# SBH_MCU.net
KiCad netlist of a schematic drawn in Altium Designer
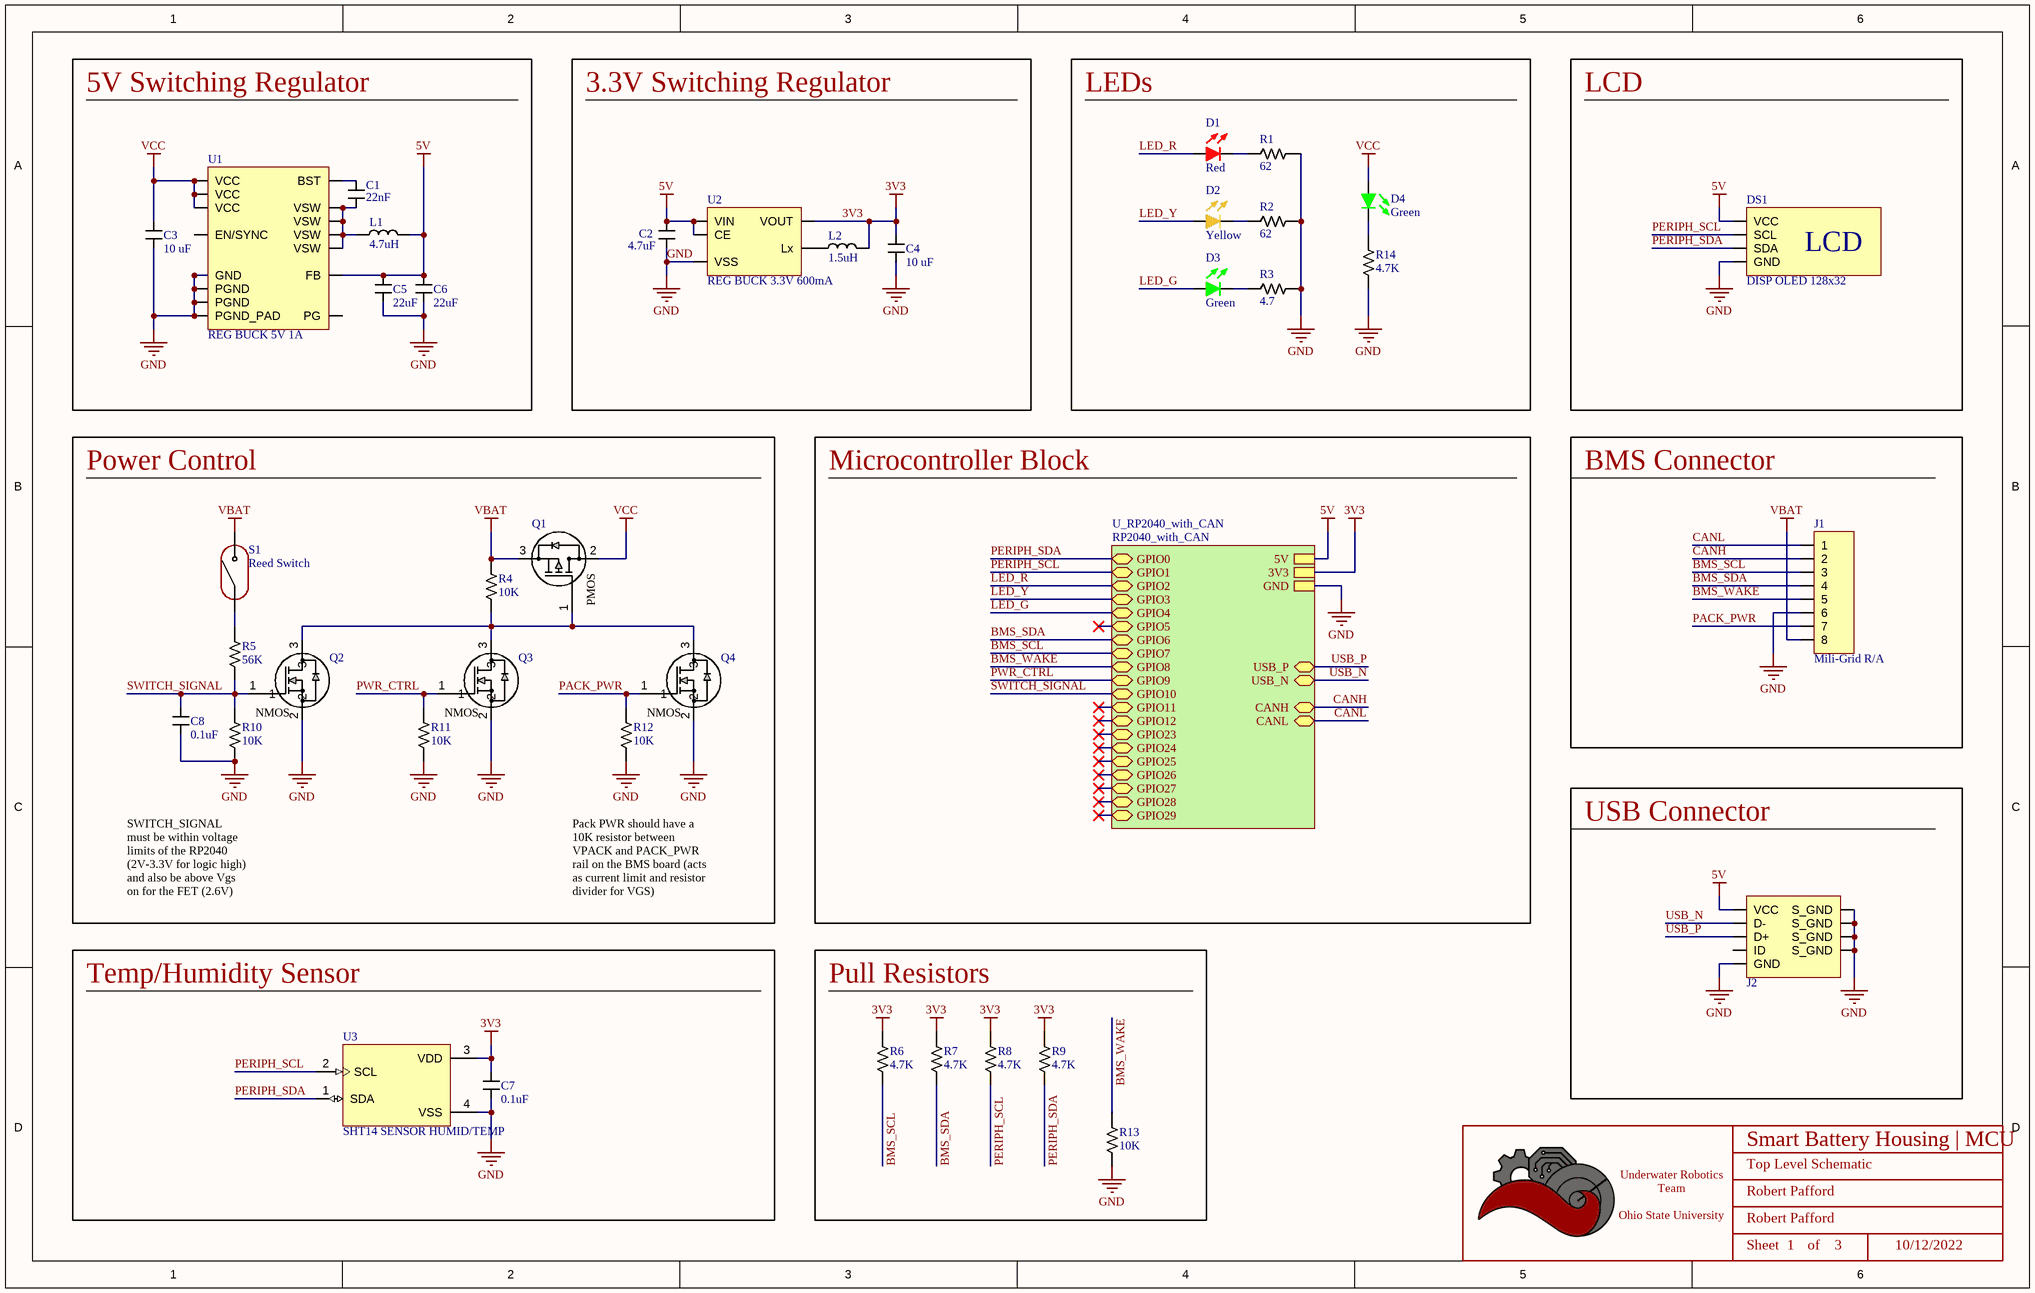
[diagram p0: SBH_MCU.SchDoc]

(export (version "E")
  (design (tool "Eeschema 10.0.6"))
  (components
    (comp (ref "*")
      (value "Title_Block")
      (footprint "LOGO")
      (description "UWRT Schematic Title Block Template\r\n\r\nCreated June 2021, Dylan Trainor")
      (libsource (lib "UWRT") (part "Title_Block"))
    )
    (comp (ref "C1")
      (value "22nF")
      (footprint "CAPACITOR_0402")
      (description "Cap 22nF 25V +/-10%\r\nCeramic 0402")
      (fields
        (field (name "TOLERANCE") "+/- 10%")
        (field (name "VOLTAGE") "25V")
        (field (name "MADE BY") "Robert Pafford")
      )
      (libsource (lib "Capacitors") (part "CAPACITOR_0.022uF_0402"))
    )
    (comp (ref "C2")
      (value "4.7uF")
      (footprint "CAPACITOR_0603")
      (description "Cap 4.7uF 6.3V +/-10%\r\nCeramic 0603")
      (fields
        (field (name "TOLERANCE") "+/- 10%")
        (field (name "VOLTAGE") "6.3V")
        (field (name "MADE BY") "Robert Pafford")
      )
      (libsource (lib "Capacitors") (part "CAPACITOR_4.7uF_0603"))
    )
    (comp (ref "C3")
      (value "10uF Ceramic 25V")
      (footprint "CAPACITOR_1206")
      (description "Cap 10uF 25V +/-10%\r\nCeramic 1206")
      (fields
        (field (name "TOLERANCE") "+/- 10%")
        (field (name "VOLTAGE") "25V")
        (field (name "VALUE (UF)") "10 uF")
        (field (name "MADE BY") "Robert Pafford")
      )
      (libsource (lib "Capacitors") (part "CAPACITOR_10uF_1206"))
    )
    (comp (ref "C4")
      (value "10uF Ceramic 6.3V")
      (footprint "CAPACITOR_0603")
      (description "Cap 10uF 6.3V +/-20%\r\nCeramic 0603")
      (fields
        (field (name "TOLERANCE") "+/- 20%")
        (field (name "VOLTAGE") "6.3V")
        (field (name "VALUE (UF)") "10 uF")
        (field (name "MADE BY") "Flip B")
      )
      (libsource (lib "Capacitors") (part "CAPACITOR_10uF_0603"))
    )
    (comp (ref "C5")
      (value "22uF")
      (footprint "CAPACITOR_0805")
      (description "Cap 22uF 10V +/-20% X5R\r\nCeramic 0805")
      (fields
        (field (name "TOLERANCE") "+/- 20%")
        (field (name "VOLTAGE") "10V")
        (field (name "MADE BY") "Robert Pafford")
      )
      (libsource (lib "Capacitors") (part "CAPACITOR_22uF_0805"))
    )
    (comp (ref "C6")
      (value "22uF")
      (footprint "CAPACITOR_0805")
      (description "Cap 22uF 10V +/-20% X5R\r\nCeramic 0805")
      (fields
        (field (name "TOLERANCE") "+/- 20%")
        (field (name "VOLTAGE") "10V")
        (field (name "MADE BY") "Robert Pafford")
      )
      (libsource (lib "Capacitors") (part "CAPACITOR_22uF_0805"))
    )
    (comp (ref "C7")
      (value "0.1uF")
      (footprint "CAPACITOR_0402")
      (description "Cap 100nF 25V +/-10%\r\nCeramic 0402")
      (fields
        (field (name "TOLERANCE") "+/- 10%")
        (field (name "VOLTAGE") "25V")
        (field (name "MADE BY") "Robert Pafford")
      )
      (libsource (lib "Capacitors") (part "CAPACITOR_0.1uF_0402"))
    )
    (comp (ref "C8")
      (value "0.1uF")
      (footprint "CAPACITOR_0402")
      (description "Cap 100nF 25V +/-10%\r\nCeramic 0402")
      (fields
        (field (name "TOLERANCE") "+/- 10%")
        (field (name "VOLTAGE") "25V")
        (field (name "MADE BY") "Robert Pafford")
      )
      (libsource (lib "Capacitors") (part "CAPACITOR_0.1uF_0402"))
    )
    (comp (ref "D1")
      (value "150060RS75000")
      (footprint "LED_0603")
      (description "LED Red Vf= 2V If = 0.020A\r\n150060RS75000")
      (fields (field (name "COLOR") "Red") (field (name "MADE BY") "Robert Pafford"))
      (libsource (lib "Diodes") (part "LED_Red_0603"))
    )
    (comp (ref "D2")
      (value "150060YS75000")
      (footprint "LED_0603")
      (description "LED Yellow Vf= 2V If = 0.020A\r\n150060YS75000")
      (fields (field (name "COLOR") "Yellow") (field (name "MADE BY") "Robert Pafford"))
      (libsource (lib "Diodes") (part "LED_Yellow_0603"))
    )
    (comp (ref "D3")
      (value "150060GS75000")
      (footprint "LED_0603")
      (description "LED Green Vf= 3.2V If = 0.025A\r\n150060GS75000")
      (fields (field (name "COLOR") "Green") (field (name "MADE BY") "Flip B"))
      (libsource (lib "Diodes") (part "LED_Green_0603_3.2V"))
    )
    (comp (ref "D4")
      (value "150060GS75000")
      (footprint "LED_0603")
      (description "LED Green Vf= 3.2V If = 0.025A\r\n150060GS75000")
      (fields (field (name "COLOR") "Green") (field (name "MADE BY") "Flip B"))
      (libsource (lib "Diodes") (part "LED_Green_0603_3.2V"))
    )
    (comp (ref "DS1")
      (value "DISP OLED 128x32")
      (footprint "OLED_I2C_128x32")
      (description "0.91'' 128x32 I2C OLED LCD Display Module")
      (fields (field (name "MADE BY") "Robert Pafford"))
      (libsource (lib "Modules") (part "OLED_I2C_128x32"))
    )
    (comp (ref "J1")
      (value "Mili-Grid R/A")
      (footprint "Molex_Mili-Grid_2x4PIN_2.00MM_RA")
      (description "Molex Mili-Grid 2.00mm pitch 8 Pos Right Angle")
      (fields (field (name "MANUFACTURER") "Molex") (field (name "CREATED BY") "Flip B"))
      (libsource (lib "Connectors") (part "CONN_MOLEX_MiliGrid_8POS_R/A"))
    )
    (comp (ref "J2")
      (value "USB_MICRO R/A")
      (footprint "CONN_MINIUSB")
      (description "Amphenol Micro USB-B\r\nUSB2.0 5 Pin Right Angle SMD")
      (fields (field (name "MANUFACTURER") "Amphenol") (field (name "CREATED BY") "Flip B"))
      (libsource (lib "Connectors") (part "CONN_MICROUSB"))
    )
    (comp (ref "L1")
      (value "4.7uH")
      (footprint "INDUCTOR_SLF7045")
      (description "4.7 µH Shielded Drum Core, Wirewound Inductor 2.1 A 36mOhm Max Nonstandard")
      (fields
        (field (name "TOLERANCE") "+/- 20%")
        (field (name "Comment") "4.7uH Shielded Drum Core")
        (field (name "MADE BY") "Robert Pafford")
      )
      (libsource (lib "Inductors") (part "INDUCTOR_4.7uH_SLF7045T"))
    )
    (comp (ref "L2")
      (value "1.5uH")
      (footprint "INDUCTOR_NR3015")
      (description "Inductor Shielded 1.5uH 1.8A +/-30%")
      (fields
        (field (name "TOLERANCE") "+/- 30%")
        (field (name "Comment") "1.5uH Shielded")
        (field (name "MADE BY") "Robert Pafford")
      )
      (libsource (lib "Inductors") (part "INDUCTOR_1.5uH_NR3015"))
    )
    (comp (ref "Q1")
      (value "DMP3056L-7")
      (footprint "SOT-23-3")
      (description "P-Channel 30V 4.3A (Ta) 1.38W (Ta) Surface Mount SOT23")
      (fields (field (name "CREATED BY") "John Ulm") (field (name "REVIEWED BY") "---"))
      (libsource (lib "Transistors") (part "DMP3056L-7"))
    )
    (comp (ref "Q2")
      (value "MOSFET N-CH 30V 5.8A SOT-23-3")
      (footprint "SOT-23-3")
      (description "N-Channel 30 V 5.8A (Ta) 1.4W (Ta) Surface Mount SOT-23-3")
      (fields (field (name "MANUFACTURER _PART_NUMBER") "AO3404A") (field (name "CREATED BY") "Dylan T"))
      (libsource (lib "Transistors") (part "AO3404A"))
    )
    (comp (ref "Q3")
      (value "MOSFET N-CH 30V 5.8A SOT-23-3")
      (footprint "SOT-23-3")
      (description "N-Channel 30 V 5.8A (Ta) 1.4W (Ta) Surface Mount SOT-23-3")
      (fields (field (name "MANUFACTURER _PART_NUMBER") "AO3404A") (field (name "CREATED BY") "Dylan T"))
      (libsource (lib "Transistors") (part "AO3404A"))
    )
    (comp (ref "Q4")
      (value "MOSFET N-CH 30V 5.8A SOT-23-3")
      (footprint "SOT-23-3")
      (description "N-Channel 30 V 5.8A (Ta) 1.4W (Ta) Surface Mount SOT-23-3")
      (fields (field (name "MANUFACTURER _PART_NUMBER") "AO3404A") (field (name "CREATED BY") "Dylan T"))
      (libsource (lib "Transistors") (part "AO3404A"))
    )
    (comp (ref "R1")
      (value "62 Ohm 1% 1/4W")
      (footprint "RESISTOR_0603")
      (description "RES SMD 62 OHM 1% 1/4W 0603")
      (fields
        (field (name "TOLERANCE") "+/- 1%")
        (field (name "VALUE  (OHMS)") "62")
        (field (name "MADE BY") "Robert Pafford")
      )
      (libsource (lib "Resistors") (part "RESISTOR_62_0603"))
    )
    (comp (ref "R2")
      (value "62 Ohm 1% 1/4W")
      (footprint "RESISTOR_0603")
      (description "RES SMD 62 OHM 1% 1/4W 0603")
      (fields
        (field (name "TOLERANCE") "+/- 1%")
        (field (name "VALUE  (OHMS)") "62")
        (field (name "MADE BY") "Robert Pafford")
      )
      (libsource (lib "Resistors") (part "RESISTOR_62_0603"))
    )
    (comp (ref "R3")
      (value "4.7 Ohm 5% 1/8W")
      (footprint "RESISTOR_0603")
      (description "RES 4.7 OHM 5% 1/8W 0603")
      (fields
        (field (name "TOLERANCE") "+/- 5%")
        (field (name "VALUE  (OHMS)") "4.7")
        (field (name "MADE BY") "Robert Pafford")
      )
      (libsource (lib "Resistors") (part "RESISTOR_4.7_0603"))
    )
    (comp (ref "R4")
      (value "10k Ohm 5% 1/10W")
      (footprint "RESISTOR_0603")
      (description "RES 10k OHM 5% 1/10W 0603")
      (fields
        (field (name "TOLERANCE") "+/- 5%")
        (field (name "VALUE  (OHMS)") "10K")
        (field (name "MADE BY") "Robert Pafford")
      )
      (libsource (lib "Resistors") (part "RESISTOR_10K_0603"))
    )
    (comp (ref "R5")
      (value "56k Ohm 1% 1/16W")
      (footprint "RESISTOR_0402")
      (description "RES 56k OHM 1% 1/16W 0402")
      (fields
        (field (name "TOLERANCE") "+/- 1%")
        (field (name "VALUE  (OHMS)") "56K")
        (field (name "MADE BY") "Robert Pafford")
      )
      (libsource (lib "Resistors") (part "RESISTOR_56K_0402"))
    )
    (comp (ref "R6")
      (value "4.7k Ohm 5% 1/10W")
      (footprint "RESISTOR_0603")
      (description "RES 4.7k OHM 5% 1/10W 0603")
      (fields
        (field (name "TOLERANCE") "+/- 5%")
        (field (name "VALUE  (OHMS)") "4.7K")
        (field (name "MADE BY") "Robert Pafford")
      )
      (libsource (lib "Resistors") (part "RESISTOR_4.7K_0603"))
    )
    (comp (ref "R7")
      (value "4.7k Ohm 5% 1/10W")
      (footprint "RESISTOR_0603")
      (description "RES 4.7k OHM 5% 1/10W 0603")
      (fields
        (field (name "TOLERANCE") "+/- 5%")
        (field (name "VALUE  (OHMS)") "4.7K")
        (field (name "MADE BY") "Robert Pafford")
      )
      (libsource (lib "Resistors") (part "RESISTOR_4.7K_0603"))
    )
    (comp (ref "R8")
      (value "4.7k Ohm 5% 1/10W")
      (footprint "RESISTOR_0603")
      (description "RES 4.7k OHM 5% 1/10W 0603")
      (fields
        (field (name "TOLERANCE") "+/- 5%")
        (field (name "VALUE  (OHMS)") "4.7K")
        (field (name "MADE BY") "Robert Pafford")
      )
      (libsource (lib "Resistors") (part "RESISTOR_4.7K_0603"))
    )
    (comp (ref "R9")
      (value "4.7k Ohm 5% 1/10W")
      (footprint "RESISTOR_0603")
      (description "RES 4.7k OHM 5% 1/10W 0603")
      (fields
        (field (name "TOLERANCE") "+/- 5%")
        (field (name "VALUE  (OHMS)") "4.7K")
        (field (name "MADE BY") "Robert Pafford")
      )
      (libsource (lib "Resistors") (part "RESISTOR_4.7K_0603"))
    )
    (comp (ref "R10")
      (value "10k Ohm 5% 1/10W")
      (footprint "RESISTOR_0603")
      (description "RES 10k OHM 5% 1/10W 0603")
      (fields
        (field (name "TOLERANCE") "+/- 5%")
        (field (name "VALUE  (OHMS)") "10K")
        (field (name "MADE BY") "Robert Pafford")
      )
      (libsource (lib "Resistors") (part "RESISTOR_10K_0603"))
    )
    (comp (ref "R11")
      (value "10k Ohm 5% 1/10W")
      (footprint "RESISTOR_0603")
      (description "RES 10k OHM 5% 1/10W 0603")
      (fields
        (field (name "TOLERANCE") "+/- 5%")
        (field (name "VALUE  (OHMS)") "10K")
        (field (name "MADE BY") "Robert Pafford")
      )
      (libsource (lib "Resistors") (part "RESISTOR_10K_0603"))
    )
    (comp (ref "R12")
      (value "10k Ohm 5% 1/10W")
      (footprint "RESISTOR_0603")
      (description "RES 10k OHM 5% 1/10W 0603")
      (fields
        (field (name "TOLERANCE") "+/- 5%")
        (field (name "VALUE  (OHMS)") "10K")
        (field (name "MADE BY") "Robert Pafford")
      )
      (libsource (lib "Resistors") (part "RESISTOR_10K_0603"))
    )
    (comp (ref "R13")
      (value "10k Ohm 5% 1/10W")
      (footprint "RESISTOR_0603")
      (description "RES 10k OHM 5% 1/10W 0603")
      (fields
        (field (name "TOLERANCE") "+/- 5%")
        (field (name "VALUE  (OHMS)") "10K")
        (field (name "MADE BY") "Robert Pafford")
      )
      (libsource (lib "Resistors") (part "RESISTOR_10K_0603"))
    )
    (comp (ref "R14")
      (value "4.7k Ohm 5% 1/10W")
      (footprint "RESISTOR_0603")
      (description "RES 4.7k OHM 5% 1/10W 0603")
      (fields
        (field (name "TOLERANCE") "+/- 5%")
        (field (name "VALUE  (OHMS)") "4.7K")
        (field (name "MADE BY") "Robert Pafford")
      )
      (libsource (lib "Resistors") (part "RESISTOR_4.7K_0603"))
    )
    (comp (ref "S1")
      (value "Reed Switch")
      (footprint "MDSR-7")
      (fields (field (name "MADE BY") "Robert Pafford"))
      (libsource (lib "Switches") (part "Reed Switch"))
    )
    (comp (ref "U1")
      (value "REG BUCK 5V 1A")
      (footprint "QFN-16 (3x3)")
      (description "Buck Switching Regulator IC Positive Fixed 5V 1 Output 1A 16-VFQFN Exposed Pad")
      (fields (field (name "MADE BY") "Robert Pafford"))
      (libsource (lib "Integrated Circuits") (part "TS30041-M050QFNR"))
    )
    (comp (ref "U2")
      (value "REG BUCK 3.3V 600mA")
      (footprint "SOT-23-5")
      (description "Buck Switching Regulator IC Positive Fixed 3.3V 1 Output 600mA SOT25")
      (fields (field (name "MADE BY") "Robert Pafford"))
      (libsource (lib "Integrated Circuits") (part "XC9236A33DMR-G"))
    )
    (comp (ref "U3")
      (value "SHT14 SENSOR HUMID/TEMP")
      (footprint "XDCR_SHT41-AD1B-R2")
      (description "Digital Relative Humidity Temperature Sensor, Â±1.8 / max 2.5 %RH, Â±0.2 Â°C, Ultra-Low-Power")
      (fields (field (name "MP") "SHT41-AD1B-R2") (field (name "MF") "Sensirion"))
      (libsource (lib "Integrated Circuits") (part "SHT41-AD1B-R2"))
    )
  )
  (nets
    (net (code "1") (name "/BMS_SCL") (class "Default")
      (node (ref "J1") (pin "3") (pinfunction "3_3") (pintype "passive"))
      (node (ref "R6") (pin "2") (pinfunction "2_2") (pintype "passive"))
    )
    (net (code "2") (name "/BMS_SDA") (class "Default")
      (node (ref "J1") (pin "4") (pinfunction "4_4") (pintype "passive"))
      (node (ref "R7") (pin "2") (pinfunction "2_2") (pintype "passive"))
    )
    (net (code "3") (name "/BMS_WAKE") (class "Default")
      (node (ref "J1") (pin "5") (pinfunction "5_5") (pintype "passive"))
      (node (ref "R13") (pin "1") (pinfunction "1_1") (pintype "passive"))
    )
    (net (code "4") (name "/CANH") (class "Default")
      (node (ref "J1") (pin "2") (pinfunction "2_2") (pintype "passive"))
    )
    (net (code "5") (name "/CANL") (class "Default")
      (node (ref "J1") (pin "1") (pinfunction "1_1") (pintype "passive"))
    )
    (net (code "16") (name "/LED_G") (class "Default")
      (node (ref "D3") (pin "1") (pinfunction "1_1") (pintype "passive"))
    )
    (net (code "17") (name "/LED_R") (class "Default")
      (node (ref "D1") (pin "1") (pinfunction "1_1") (pintype "passive"))
    )
    (net (code "18") (name "/LED_Y") (class "Default")
      (node (ref "D2") (pin "1") (pinfunction "1_1") (pintype "passive"))
    )
    (net (code "19") (name "/PACK_PWR") (class "Default")
      (node (ref "J1") (pin "7") (pinfunction "7_7") (pintype "passive"))
      (node (ref "Q4") (pin "1") (pinfunction "1_1") (pintype "passive"))
      (node (ref "R12") (pin "1") (pinfunction "1_1") (pintype "passive"))
    )
    (net (code "20") (name "/PERIPH_SCL") (class "Default")
      (node (ref "DS1") (pin "3") (pinfunction "SCL_3") (pintype "passive"))
      (node (ref "R8") (pin "2") (pinfunction "2_2") (pintype "passive"))
      (node (ref "U3") (pin "2") (pinfunction "SCL_2") (pintype "input"))
    )
    (net (code "21") (name "/PERIPH_SDA") (class "Default")
      (node (ref "DS1") (pin "4") (pinfunction "SDA_4") (pintype "passive"))
      (node (ref "R9") (pin "2") (pinfunction "2_2") (pintype "passive"))
      (node (ref "U3") (pin "1") (pinfunction "SDA_1") (pintype "bidirectional"))
    )
    (net (code "22") (name "/PWR_CTRL") (class "Default")
      (node (ref "Q3") (pin "1") (pinfunction "1_1") (pintype "passive"))
      (node (ref "R11") (pin "1") (pinfunction "1_1") (pintype "passive"))
    )
    (net (code "23") (name "/SWITCH_SIGNAL") (class "Default")
      (node (ref "C8") (pin "1") (pinfunction "1_1") (pintype "passive"))
      (node (ref "Q2") (pin "1") (pinfunction "1_1") (pintype "passive"))
      (node (ref "R10") (pin "1") (pinfunction "1_1") (pintype "passive"))
      (node (ref "R5") (pin "2") (pinfunction "2_2") (pintype "passive"))
    )
    (net (code "24") (name "/USB_N") (class "Default")
      (node (ref "J2") (pin "2") (pinfunction "D-_2") (pintype "passive"))
    )
    (net (code "25") (name "/USB_P") (class "Default")
      (node (ref "J2") (pin "3") (pinfunction "D+_3") (pintype "passive"))
    )
    (net (code "26") (name "3V3") (class "Default")
      (node (ref "C4") (pin "1") (pinfunction "1_1") (pintype "passive"))
      (node (ref "C7") (pin "1") (pinfunction "1_1") (pintype "passive"))
      (node (ref "L2") (pin "1") (pinfunction "1_1") (pintype "passive"))
      (node (ref "R6") (pin "1") (pinfunction "1_1") (pintype "passive"))
      (node (ref "R7") (pin "1") (pinfunction "1_1") (pintype "passive"))
      (node (ref "R8") (pin "1") (pinfunction "1_1") (pintype "passive"))
      (node (ref "R9") (pin "1") (pinfunction "1_1") (pintype "passive"))
      (node (ref "U2") (pin "4") (pinfunction "VOUT_4") (pintype "passive"))
      (node (ref "U3") (pin "3") (pinfunction "VDD_3") (pintype "power_in"))
    )
    (net (code "27") (name "5V") (class "Default")
      (node (ref "C2") (pin "1") (pinfunction "1_1") (pintype "passive"))
      (node (ref "C5") (pin "1") (pinfunction "1_1") (pintype "passive"))
      (node (ref "C6") (pin "1") (pinfunction "1_1") (pintype "passive"))
      (node (ref "DS1") (pin "2") (pinfunction "VCC_2") (pintype "passive"))
      (node (ref "J2") (pin "1") (pinfunction "VCC_1") (pintype "passive"))
      (node (ref "L1") (pin "1") (pinfunction "1_1") (pintype "passive"))
      (node (ref "U1") (pin "5") (pinfunction "FB_5") (pintype "passive"))
      (node (ref "U2") (pin "1") (pinfunction "VIN_1") (pintype "passive"))
      (node (ref "U2") (pin "3") (pinfunction "CE_3") (pintype "passive"))
    )
    (net (code "28") (name "GND") (class "Default")
      (node (ref "C2") (pin "2") (pinfunction "2_2") (pintype "passive"))
      (node (ref "C3") (pin "2") (pinfunction "2_2") (pintype "passive"))
      (node (ref "C4") (pin "2") (pinfunction "2_2") (pintype "passive"))
      (node (ref "C5") (pin "2") (pinfunction "2_2") (pintype "passive"))
      (node (ref "C6") (pin "2") (pinfunction "2_2") (pintype "passive"))
      (node (ref "C7") (pin "2") (pinfunction "2_2") (pintype "passive"))
      (node (ref "C8") (pin "2") (pinfunction "2_2") (pintype "passive"))
      (node (ref "DS1") (pin "1") (pinfunction "GND_1") (pintype "passive"))
      (node (ref "J1") (pin "6") (pinfunction "6_6") (pintype "passive"))
      (node (ref "J2") (pin "5") (pinfunction "GND_5") (pintype "passive"))
      (node (ref "J2") (pin "6") (pinfunction "S_GND_6") (pintype "passive"))
      (node (ref "J2") (pin "7") (pinfunction "S_GND_7") (pintype "passive"))
      (node (ref "J2") (pin "8") (pinfunction "S_GND_8") (pintype "passive"))
      (node (ref "J2") (pin "9") (pinfunction "S_GND_9") (pintype "passive"))
      (node (ref "Q2") (pin "2") (pinfunction "2_2") (pintype "passive"))
      (node (ref "Q3") (pin "2") (pinfunction "2_2") (pintype "passive"))
      (node (ref "Q4") (pin "2") (pinfunction "2_2") (pintype "passive"))
      (node (ref "R1") (pin "1") (pinfunction "1_1") (pintype "passive"))
      (node (ref "R10") (pin "2") (pinfunction "2_2") (pintype "passive"))
      (node (ref "R11") (pin "2") (pinfunction "2_2") (pintype "passive"))
      (node (ref "R12") (pin "2") (pinfunction "2_2") (pintype "passive"))
      (node (ref "R13") (pin "2") (pinfunction "2_2") (pintype "passive"))
      (node (ref "R14") (pin "2") (pinfunction "2_2") (pintype "passive"))
      (node (ref "R2") (pin "1") (pinfunction "1_1") (pintype "passive"))
      (node (ref "R3") (pin "1") (pinfunction "1_1") (pintype "passive"))
      (node (ref "U1") (pin "14") (pinfunction "PGND_14") (pintype "power_in"))
      (node (ref "U1") (pin "15") (pinfunction "PGND_15") (pintype "power_in"))
      (node (ref "U1") (pin "17") (pinfunction "PGND_PAD_17") (pintype "power_in"))
      (node (ref "U1") (pin "4") (pinfunction "GND_4") (pintype "power_in"))
      (node (ref "U2") (pin "2") (pinfunction "VSS_2") (pintype "passive"))
      (node (ref "U3") (pin "4") (pinfunction "VSS_4") (pintype "power_in"))
    )
    (net (code "29") (name "Net-(C1-Pad2)") (class "Default")
      (node (ref "C1") (pin "2") (pinfunction "2_2") (pintype "passive"))
      (node (ref "L1") (pin "2") (pinfunction "2_2") (pintype "passive"))
      (node (ref "U1") (pin "1") (pinfunction "VSW_1") (pintype "power_in"))
      (node (ref "U1") (pin "12") (pinfunction "VSW_12") (pintype "power_in"))
      (node (ref "U1") (pin "13") (pinfunction "VSW_13") (pintype "power_in"))
      (node (ref "U1") (pin "16") (pinfunction "VSW_16") (pintype "passive"))
    )
    (net (code "30") (name "Net-(D1-Pad2)") (class "Default")
      (node (ref "D1") (pin "2") (pinfunction "2_2") (pintype "passive"))
      (node (ref "R1") (pin "2") (pinfunction "2_2") (pintype "passive"))
    )
    (net (code "31") (name "Net-(D2-Pad2)") (class "Default")
      (node (ref "D2") (pin "2") (pinfunction "2_2") (pintype "passive"))
      (node (ref "R2") (pin "2") (pinfunction "2_2") (pintype "passive"))
    )
    (net (code "32") (name "Net-(D3-Pad2)") (class "Default")
      (node (ref "D3") (pin "2") (pinfunction "2_2") (pintype "passive"))
      (node (ref "R3") (pin "2") (pinfunction "2_2") (pintype "passive"))
    )
    (net (code "33") (name "Net-(D4-Pad2)") (class "Default")
      (node (ref "D4") (pin "2") (pinfunction "2_2") (pintype "passive"))
      (node (ref "R14") (pin "1") (pinfunction "1_1") (pintype "passive"))
    )
    (net (code "34") (name "Net-(Q1-Pad1)") (class "Default")
      (node (ref "Q1") (pin "1") (pinfunction "1_1") (pintype "passive"))
      (node (ref "Q2") (pin "3") (pinfunction "3_3") (pintype "passive"))
      (node (ref "Q3") (pin "3") (pinfunction "3_3") (pintype "passive"))
      (node (ref "Q4") (pin "3") (pinfunction "3_3") (pintype "passive"))
      (node (ref "R4") (pin "2") (pinfunction "2_2") (pintype "passive"))
    )
    (net (code "35") (name "Net-(R5-Pad1)") (class "Default")
      (node (ref "R5") (pin "1") (pinfunction "1_1") (pintype "passive"))
      (node (ref "S1") (pin "1") (pintype "passive"))
    )
    (net (code "36") (name "Net-(U1-BST)") (class "Default")
      (node (ref "C1") (pin "1") (pinfunction "1_1") (pintype "passive"))
      (node (ref "U1") (pin "10") (pinfunction "BST_10") (pintype "passive"))
    )
    (net (code "37") (name "Net-(U2-Lx)") (class "Default")
      (node (ref "L2") (pin "2") (pinfunction "2_2") (pintype "passive"))
      (node (ref "U2") (pin "5") (pinfunction "Lx_5") (pintype "passive"))
    )
    (net (code "38") (name "VBAT") (class "Default")
      (node (ref "J1") (pin "8") (pinfunction "8_8") (pintype "passive"))
      (node (ref "Q1") (pin "3") (pinfunction "3_3") (pintype "passive"))
      (node (ref "R4") (pin "1") (pinfunction "1_1") (pintype "passive"))
      (node (ref "S1") (pin "2") (pintype "passive"))
    )
    (net (code "39") (name "VCC") (class "Default")
      (node (ref "C3") (pin "1") (pinfunction "1_1") (pintype "passive"))
      (node (ref "D4") (pin "1") (pinfunction "1_1") (pintype "passive"))
      (node (ref "Q1") (pin "2") (pinfunction "2_2") (pintype "passive"))
      (node (ref "U1") (pin "11") (pinfunction "VCC_11") (pintype "power_in"))
      (node (ref "U1") (pin "2") (pinfunction "VCC_2") (pintype "power_in"))
      (node (ref "U1") (pin "3") (pinfunction "VCC_3") (pintype "power_in"))
    )
    (net (code "40") (name "unconnected-(J2-ID-Pad4)") (class "Default")
      (node (ref "J2") (pin "4") (pinfunction "ID_4") (pintype "passive"))
    )
    (net (code "41") (name "unconnected-(U1-EN{slash}SYNC-Pad9)") (class "Default")
      (node (ref "U1") (pin "9") (pinfunction "EN/SYNC_9") (pintype "passive"))
    )
    (net (code "42") (name "unconnected-(U1-PG-Pad8)") (class "Default")
      (node (ref "U1") (pin "8") (pinfunction "PG_8") (pintype "passive"))
    )
  )
)
